# band4_0.net
KiCad netlist of a schematic drawn in EAGLE
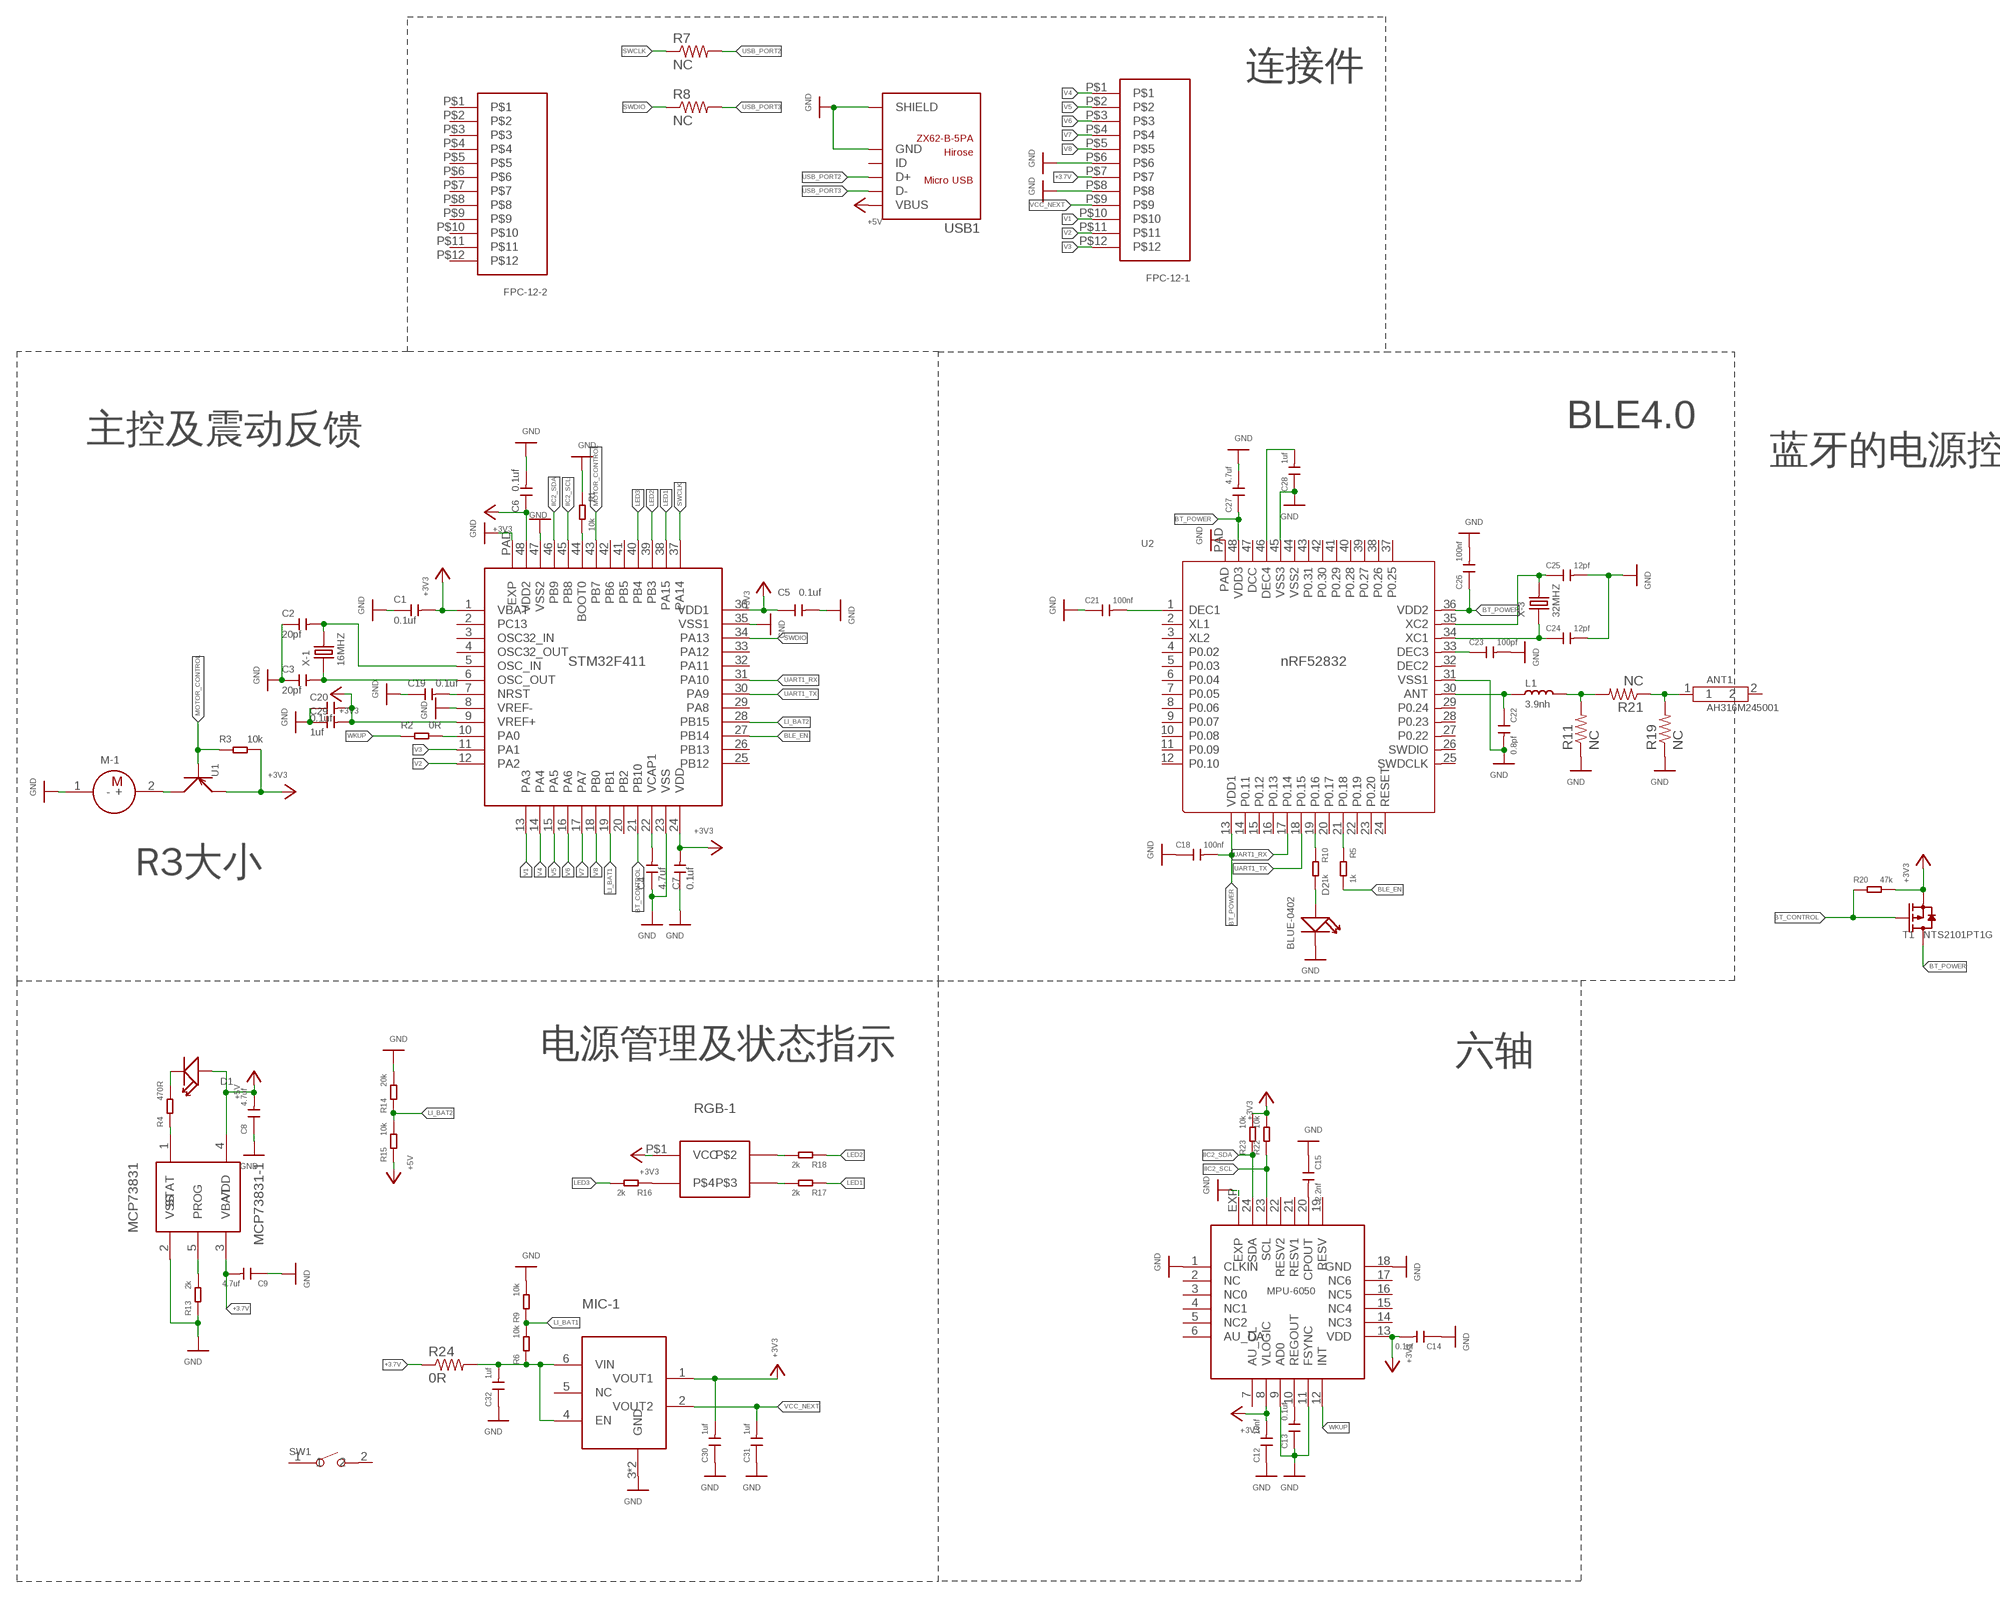
[diagram p0: schematic, sheet 1]

(export (version "E")
  (design (tool "Eeschema 10.0.6"))
  (components
    (comp (ref "ANT1")
      (value "AH316M245001")
      (footprint "eagle-import:ANT2-SMD-3.2X1.6X0.5MM")
      (fields (field (name "MPN") "AH316M245001-T"))
      (libsource (lib "eagle-import") (part "ANTENNA-2.4GHZ-AH316M245001-T"))
    )
    (comp (ref "C1")
      (value "0.1uf")
      (footprint "eagle-import:C0402")
      (fields (field (name "MPN") "CC0402BRNPO9BNR50"))
      (libsource (lib "eagle-import") (part "C(0402)"))
    )
    (comp (ref "C2")
      (value "20pf")
      (footprint "eagle-import:C0402")
      (fields (field (name "MPN") "CC0402BRNPO9BNR50"))
      (libsource (lib "eagle-import") (part "C(0402)"))
    )
    (comp (ref "C3")
      (value "20pf")
      (footprint "eagle-import:C0402")
      (fields (field (name "MPN") "CC0402BRNPO9BNR50"))
      (libsource (lib "eagle-import") (part "C(0402)"))
    )
    (comp (ref "C4")
      (value "4.7uf")
      (footprint "eagle-import:C0402")
      (fields (field (name "MPN") "CC0402BRNPO9BNR50"))
      (libsource (lib "eagle-import") (part "C(0402)"))
    )
    (comp (ref "C5")
      (value "0.1uf")
      (footprint "eagle-import:C0402")
      (fields (field (name "MPN") "CC0402BRNPO9BNR50"))
      (libsource (lib "eagle-import") (part "C(0402)"))
    )
    (comp (ref "C6")
      (value "0.1uf")
      (footprint "eagle-import:C0402")
      (fields (field (name "MPN") "CC0402BRNPO9BNR50"))
      (libsource (lib "eagle-import") (part "C(0402)"))
    )
    (comp (ref "C7")
      (value "0.1uf")
      (footprint "eagle-import:C0402")
      (fields (field (name "MPN") "CC0402BRNPO9BNR50"))
      (libsource (lib "eagle-import") (part "C(0402)"))
    )
    (comp (ref "C8")
      (value "4.7uf")
      (footprint "eagle-import:C0402")
      (fields (field (name "MPN") "CC0402BRNPO9BNR50"))
      (libsource (lib "eagle-import") (part "C(0402)"))
    )
    (comp (ref "C9")
      (value "4.7uf")
      (footprint "eagle-import:C0402")
      (fields (field (name "MPN") "CC0402BRNPO9BNR50"))
      (libsource (lib "eagle-import") (part "C(0402)"))
    )
    (comp (ref "C12")
      (value "10nf")
      (footprint "eagle-import:C0402")
      (fields (field (name "MPN") "CC0402BRNPO9BNR50"))
      (libsource (lib "eagle-import") (part "C(0402)"))
    )
    (comp (ref "C13")
      (value "0.1uf")
      (footprint "eagle-import:C0402")
      (fields (field (name "MPN") "CC0402BRNPO9BNR50"))
      (libsource (lib "eagle-import") (part "C(0402)"))
    )
    (comp (ref "C14")
      (value "0.1uf")
      (footprint "eagle-import:C0402")
      (fields (field (name "MPN") "CC0402BRNPO9BNR50"))
      (libsource (lib "eagle-import") (part "C(0402)"))
    )
    (comp (ref "C15")
      (value "2.2nf")
      (footprint "eagle-import:C0402")
      (fields (field (name "MPN") "CC0402BRNPO9BNR50"))
      (libsource (lib "eagle-import") (part "C(0402)"))
    )
    (comp (ref "C18")
      (value "100nf")
      (footprint "eagle-import:C0402")
      (fields (field (name "MPN") "CC0402BRNPO9BNR50"))
      (libsource (lib "eagle-import") (part "C(0402)"))
    )
    (comp (ref "C19")
      (value "0.1uf")
      (footprint "eagle-import:C0402")
      (fields (field (name "MPN") "CC0402BRNPO9BNR50"))
      (libsource (lib "eagle-import") (part "C(0402)"))
    )
    (comp (ref "C20")
      (value "0.1uf")
      (footprint "eagle-import:C0402")
      (fields (field (name "MPN") "CC0402BRNPO9BNR50"))
      (libsource (lib "eagle-import") (part "C(0402)"))
    )
    (comp (ref "C21")
      (value "100nf")
      (footprint "eagle-import:C0402")
      (fields (field (name "MPN") "CC0402BRNPO9BNR50"))
      (libsource (lib "eagle-import") (part "C(0402)"))
    )
    (comp (ref "C22")
      (value "0.8pf")
      (footprint "eagle-import:C0402")
      (fields (field (name "MPN") "CC0402BRNPO9BNR50"))
      (libsource (lib "eagle-import") (part "C(0402)"))
    )
    (comp (ref "C23")
      (value "100pf")
      (footprint "eagle-import:C0402")
      (fields (field (name "MPN") "CC0402BRNPO9BNR50"))
      (libsource (lib "eagle-import") (part "C(0402)"))
    )
    (comp (ref "C24")
      (value "12pf")
      (footprint "eagle-import:C0402")
      (fields (field (name "MPN") "CC0402BRNPO9BNR50"))
      (libsource (lib "eagle-import") (part "C(0402)"))
    )
    (comp (ref "C25")
      (value "12pf")
      (footprint "eagle-import:C0402")
      (fields (field (name "MPN") "CC0402BRNPO9BNR50"))
      (libsource (lib "eagle-import") (part "C(0402)"))
    )
    (comp (ref "C26")
      (value "100nf")
      (footprint "eagle-import:C0402")
      (fields (field (name "MPN") "CC0402BRNPO9BNR50"))
      (libsource (lib "eagle-import") (part "C(0402)"))
    )
    (comp (ref "C27")
      (value "4.7uf")
      (footprint "eagle-import:C0402")
      (fields (field (name "MPN") "CC0402BRNPO9BNR50"))
      (libsource (lib "eagle-import") (part "C(0402)"))
    )
    (comp (ref "C28")
      (value "1uf")
      (footprint "eagle-import:C0402")
      (fields (field (name "MPN") "CC0402BRNPO9BNR50"))
      (libsource (lib "eagle-import") (part "C(0402)"))
    )
    (comp (ref "C29")
      (value "1uf")
      (footprint "eagle-import:C0402")
      (fields (field (name "MPN") "CC0402BRNPO9BNR50"))
      (libsource (lib "eagle-import") (part "C(0402)"))
    )
    (comp (ref "C30")
      (value "1uf")
      (footprint "eagle-import:C0402")
      (fields (field (name "MPN") "CC0402BRNPO9BNR50"))
      (libsource (lib "eagle-import") (part "C(0402)"))
    )
    (comp (ref "C31")
      (value "1uf")
      (footprint "eagle-import:C0402")
      (fields (field (name "MPN") "CC0402BRNPO9BNR50"))
      (libsource (lib "eagle-import") (part "C(0402)"))
    )
    (comp (ref "C32")
      (value "1uf")
      (footprint "eagle-import:C0402")
      (fields (field (name "MPN") "CC0402BRNPO9BNR50"))
      (libsource (lib "eagle-import") (part "C(0402)"))
    )
    (comp (ref "D1")
      (value "LED-(0402)")
      (footprint "eagle-import:LED-0402")
      (fields (field (name "MPN") "BL-HB337A-AV-TRB"))
      (libsource (lib "eagle-import") (part "LED-(0402)"))
    )
    (comp (ref "D2")
      (value "BLUE-0402")
      (footprint "eagle-import:LED-0402")
      (fields (field (name "MPN") "BL-HB337A-AV-TRB"))
      (libsource (lib "eagle-import") (part "LED-(0402)"))
    )
    (comp (ref "FPC-12-1")
      (value "FPC-12")
      (footprint "eagle-import:FPC-12")
      (libsource (lib "eagle-import") (part "FPC-12"))
    )
    (comp (ref "FPC-12-2")
      (value "FPC-12")
      (footprint "eagle-import:FPC-12")
      (libsource (lib "eagle-import") (part "FPC-12"))
    )
    (comp (ref "L1")
      (value "3.9nh")
      (footprint "eagle-import:L0402")
      (libsource (lib "eagle-import") (part "INDUCTOR(0402)"))
    )
    (comp (ref "M-1")
      (value "MOTOR")
      (footprint "eagle-import:MOTOR")
      (libsource (lib "eagle-import") (part "MOTOR"))
    )
    (comp (ref "MCP73831-1")
      (value "MCP73831")
      (footprint "eagle-import:SOT23-5")
      (libsource (lib "eagle-import") (part "MCP73831"))
    )
    (comp (ref "MCU-1")
      (value "STM32F411")
      (footprint "eagle-import:QFN48G-0.5-7X7MM")
      (libsource (lib "eagle-import") (part "STM32F411"))
    )
    (comp (ref "MIC-1")
      (value "MIC5528")
      (footprint "eagle-import:THIN-DFN")
      (libsource (lib "eagle-import") (part "MIC5528"))
    )
    (comp (ref "MPU6050-1")
      (value "MPU-6050")
      (footprint "eagle-import:QFN24-4X4")
      (libsource (lib "eagle-import") (part "MPU-6050"))
    )
    (comp (ref "R1")
      (value "10k")
      (footprint "eagle-import:R0402")
      (fields (field (name "MPN") "RC0402JR-070RL"))
      (libsource (lib "eagle-import") (part "RES-(0402)"))
    )
    (comp (ref "R2")
      (value "0R")
      (footprint "eagle-import:R0402")
      (fields (field (name "MPN") "RC0402JR-070RL"))
      (libsource (lib "eagle-import") (part "RES-(0402)"))
    )
    (comp (ref "R3")
      (value "10k")
      (footprint "eagle-import:R0402")
      (fields (field (name "MPN") "RC0402JR-070RL"))
      (libsource (lib "eagle-import") (part "RES-(0402)"))
    )
    (comp (ref "R4")
      (value "470R")
      (footprint "eagle-import:R0402")
      (fields (field (name "MPN") "RC0402JR-070RL"))
      (libsource (lib "eagle-import") (part "RES-(0402)"))
    )
    (comp (ref "R5")
      (value "1k")
      (footprint "eagle-import:R0402")
      (fields (field (name "MPN") "RC0402JR-070RL"))
      (libsource (lib "eagle-import") (part "RES-(0402)"))
    )
    (comp (ref "R6")
      (value "10k")
      (footprint "eagle-import:R0402")
      (fields (field (name "MPN") "RC0402JR-070RL"))
      (libsource (lib "eagle-import") (part "RES-(0402)"))
    )
    (comp (ref "R7")
      (value "NC")
      (footprint "eagle-import:0201")
      (libsource (lib "eagle-import") (part "R_0201"))
    )
    (comp (ref "R8")
      (value "NC")
      (footprint "eagle-import:0201")
      (libsource (lib "eagle-import") (part "R_0201"))
    )
    (comp (ref "R9")
      (value "10k")
      (footprint "eagle-import:R0402")
      (fields (field (name "MPN") "RC0402JR-070RL"))
      (libsource (lib "eagle-import") (part "RES-(0402)"))
    )
    (comp (ref "R10")
      (value "1k")
      (footprint "eagle-import:R0402")
      (fields (field (name "MPN") "RC0402JR-070RL"))
      (libsource (lib "eagle-import") (part "RES-(0402)"))
    )
    (comp (ref "R11")
      (value "NC")
      (footprint "eagle-import:0201")
      (libsource (lib "eagle-import") (part "R_0201"))
    )
    (comp (ref "R13")
      (value "2k")
      (footprint "eagle-import:R0402")
      (fields (field (name "MPN") "RC0402JR-070RL"))
      (libsource (lib "eagle-import") (part "RES-(0402)"))
    )
    (comp (ref "R14")
      (value "20k")
      (footprint "eagle-import:R0402")
      (fields (field (name "MPN") "RC0402JR-070RL"))
      (libsource (lib "eagle-import") (part "RES-(0402)"))
    )
    (comp (ref "R15")
      (value "10k")
      (footprint "eagle-import:R0402")
      (fields (field (name "MPN") "RC0402JR-070RL"))
      (libsource (lib "eagle-import") (part "RES-(0402)"))
    )
    (comp (ref "R16")
      (value "2k")
      (footprint "eagle-import:R0402")
      (fields (field (name "MPN") "RC0402JR-070RL"))
      (libsource (lib "eagle-import") (part "RES-(0402)"))
    )
    (comp (ref "R17")
      (value "2k")
      (footprint "eagle-import:R0402")
      (fields (field (name "MPN") "RC0402JR-070RL"))
      (libsource (lib "eagle-import") (part "RES-(0402)"))
    )
    (comp (ref "R18")
      (value "2k")
      (footprint "eagle-import:R0402")
      (fields (field (name "MPN") "RC0402JR-070RL"))
      (libsource (lib "eagle-import") (part "RES-(0402)"))
    )
    (comp (ref "R19")
      (value "NC")
      (footprint "eagle-import:0201")
      (libsource (lib "eagle-import") (part "R_0201"))
    )
    (comp (ref "R20")
      (value "47k")
      (footprint "eagle-import:R0402")
      (fields (field (name "MPN") "RC0402JR-070RL"))
      (libsource (lib "eagle-import") (part "RES-(0402)"))
    )
    (comp (ref "R21")
      (value "NC")
      (footprint "eagle-import:0201")
      (libsource (lib "eagle-import") (part "R_0201"))
    )
    (comp (ref "R22")
      (value "10k")
      (footprint "eagle-import:R0402")
      (fields (field (name "MPN") "RC0402JR-070RL"))
      (libsource (lib "eagle-import") (part "RES-(0402)"))
    )
    (comp (ref "R23")
      (value "10k")
      (footprint "eagle-import:R0402")
      (fields (field (name "MPN") "RC0402JR-070RL"))
      (libsource (lib "eagle-import") (part "RES-(0402)"))
    )
    (comp (ref "R24")
      (value "0R")
      (footprint "eagle-import:0201")
      (libsource (lib "eagle-import") (part "R_0201"))
    )
    (comp (ref "RGB-1")
      (value "RGB-LED")
      (footprint "eagle-import:RGB-LED")
      (libsource (lib "eagle-import") (part "RGB-LED"))
    )
    (comp (ref "SW1")
      (value "SMD-BUTTON(2P-6.0X3.0X2.5MM)-DHT-1163S")
      (footprint "eagle-import:SW2-4.0-6.0X3.0X2.5MM")
      (libsource (lib "eagle-import") (part "SMD-BUTTON(2P-6.0X3.0X2.5MM)-DHT-1163S"))
    )
    (comp (ref "T1")
      (value "NTS2101PT1G")
      (footprint "eagle-import:SC70")
      (libsource (lib "eagle-import") (part "NTS2101PT1G"))
    )
    (comp (ref "U1")
      (value "PNP")
      (footprint "eagle-import:PNP")
      (libsource (lib "eagle-import") (part "PNP"))
    )
    (comp (ref "U2")
      (value "RF-51822")
      (footprint "eagle-import:QFN48G-0.4-6X6MM")
      (libsource (lib "eagle-import") (part "IC-NRF-52832(QFN48)"))
    )
    (comp (ref "USB1")
      (value "ZX62-B-5PA")
      (footprint "eagle-import:MICRO-USB5+6P-SMD-0.65-AB")
      (libsource (lib "eagle-import") (part "MICRO-USB-SMD(ZX62-B-5PA)"))
    )
    (comp (ref "X-1")
      (value "16MHZ")
      (footprint "eagle-import:16MHZ")
      (libsource (lib "eagle-import") (part "16MHZ"))
    )
    (comp (ref "X-3")
      (value "32MHZ")
      (footprint "eagle-import:16MHZ")
      (libsource (lib "eagle-import") (part "16MHZ"))
    )
  )
  (nets
    (net (code "1") (name "+3.7V") (class "Default")
      (node (ref "C9") (pin "2") (pinfunction "2_2") (pintype "passive"))
      (node (ref "FPC-12-1") (pin "P$7") (pinfunction "P$7_P$7") (pintype "bidirectional"))
      (node (ref "MCP73831-1") (pin "3") (pinfunction "VBAT_3") (pintype "bidirectional"))
      (node (ref "R24") (pin "1") (pinfunction "1_1") (pintype "passive"))
    )
    (net (code "2") (name "+3V3") (class "Default")
      (node (ref "C1") (pin "2") (pinfunction "2_2") (pintype "passive"))
      (node (ref "C12") (pin "2") (pinfunction "2_2") (pintype "passive"))
      (node (ref "C14") (pin "2") (pinfunction "2_2") (pintype "passive"))
      (node (ref "C20") (pin "2") (pinfunction "2_2") (pintype "passive"))
      (node (ref "C29") (pin "2") (pinfunction "2_2") (pintype "passive"))
      (node (ref "C30") (pin "2") (pinfunction "2_2") (pintype "passive"))
      (node (ref "C5") (pin "1") (pinfunction "1_1") (pintype "passive"))
      (node (ref "C6") (pin "1") (pinfunction "1_1") (pintype "passive"))
      (node (ref "C7") (pin "2") (pinfunction "2_2") (pintype "passive"))
      (node (ref "MCU-1") (pin "1") (pinfunction "VBAT_1") (pintype "bidirectional"))
      (node (ref "MCU-1") (pin "24") (pinfunction "VDD_24") (pintype "bidirectional"))
      (node (ref "MCU-1") (pin "36") (pinfunction "VDD1_36") (pintype "bidirectional"))
      (node (ref "MCU-1") (pin "48") (pinfunction "VDD2_48") (pintype "bidirectional"))
      (node (ref "MCU-1") (pin "9") (pinfunction "VREF+_9") (pintype "bidirectional"))
      (node (ref "MIC-1") (pin "1") (pinfunction "VOUT1_1") (pintype "bidirectional"))
      (node (ref "MPU6050-1") (pin "13") (pinfunction "VDD_13") (pintype "bidirectional"))
      (node (ref "MPU6050-1") (pin "8") (pinfunction "VLOGIC_8") (pintype "bidirectional"))
      (node (ref "R20") (pin "2") (pinfunction "2_2") (pintype "passive"))
      (node (ref "R22") (pin "2") (pinfunction "2_2") (pintype "passive"))
      (node (ref "R23") (pin "2") (pinfunction "2_2") (pintype "passive"))
      (node (ref "R3") (pin "2") (pinfunction "2_2") (pintype "passive"))
      (node (ref "RGB-1") (pin "P$1") (pinfunction "VCC_P$1") (pintype "bidirectional"))
      (node (ref "T1") (pin "2") (pinfunction "S_2") (pintype "passive"))
      (node (ref "U1") (pin "2") (pinfunction "E_2") (pintype "passive"))
    )
    (net (code "3") (name "+5V") (class "Default")
      (node (ref "C8") (pin "2") (pinfunction "2_2") (pintype "passive"))
      (node (ref "D1") (pin "+") (pinfunction "+_+") (pintype "passive"))
      (node (ref "MCP73831-1") (pin "4") (pinfunction "VDD_4") (pintype "bidirectional"))
      (node (ref "R15") (pin "1") (pinfunction "1_1") (pintype "passive"))
      (node (ref "USB1") (pin "1") (pinfunction "VBUS_1") (pintype "power_in"))
    )
    (net (code "4") (name "BLE_EN") (class "Default")
      (node (ref "MCU-1") (pin "27") (pinfunction "PB14_27") (pintype "bidirectional"))
      (node (ref "R5") (pin "2") (pinfunction "2_2") (pintype "passive"))
    )
    (net (code "5") (name "BT_CONTROL") (class "Default")
      (node (ref "MCU-1") (pin "21") (pinfunction "PB10_21") (pintype "bidirectional"))
      (node (ref "R20") (pin "1") (pinfunction "1_1") (pintype "passive"))
      (node (ref "T1") (pin "1") (pinfunction "G_1") (pintype "passive"))
    )
    (net (code "6") (name "BT_POWER") (class "Default")
      (node (ref "C18") (pin "2") (pinfunction "2_2") (pintype "passive"))
      (node (ref "C26") (pin "1") (pinfunction "1_1") (pintype "passive"))
      (node (ref "C27") (pin "1") (pinfunction "1_1") (pintype "passive"))
      (node (ref "T1") (pin "3") (pinfunction "D_3") (pintype "passive"))
      (node (ref "U2") (pin "13") (pinfunction "VDD1_13") (pintype "bidirectional"))
      (node (ref "U2") (pin "36") (pinfunction "VDD2_36") (pintype "bidirectional"))
      (node (ref "U2") (pin "48") (pinfunction "VDD3_48") (pintype "bidirectional"))
    )
    (net (code "7") (name "GND") (class "Default")
      (node (ref "C1") (pin "1") (pinfunction "1_1") (pintype "passive"))
      (node (ref "C12") (pin "1") (pinfunction "1_1") (pintype "passive"))
      (node (ref "C13") (pin "1") (pinfunction "1_1") (pintype "passive"))
      (node (ref "C14") (pin "1") (pinfunction "1_1") (pintype "passive"))
      (node (ref "C15") (pin "1") (pinfunction "1_1") (pintype "passive"))
      (node (ref "C18") (pin "1") (pinfunction "1_1") (pintype "passive"))
      (node (ref "C19") (pin "1") (pinfunction "1_1") (pintype "passive"))
      (node (ref "C2") (pin "1") (pinfunction "1_1") (pintype "passive"))
      (node (ref "C20") (pin "1") (pinfunction "1_1") (pintype "passive"))
      (node (ref "C21") (pin "1") (pinfunction "1_1") (pintype "passive"))
      (node (ref "C22") (pin "2") (pinfunction "2_2") (pintype "passive"))
      (node (ref "C23") (pin "2") (pinfunction "2_2") (pintype "passive"))
      (node (ref "C24") (pin "2") (pinfunction "2_2") (pintype "passive"))
      (node (ref "C25") (pin "2") (pinfunction "2_2") (pintype "passive"))
      (node (ref "C26") (pin "2") (pinfunction "2_2") (pintype "passive"))
      (node (ref "C27") (pin "2") (pinfunction "2_2") (pintype "passive"))
      (node (ref "C28") (pin "1") (pinfunction "1_1") (pintype "passive"))
      (node (ref "C29") (pin "1") (pinfunction "1_1") (pintype "passive"))
      (node (ref "C3") (pin "1") (pinfunction "1_1") (pintype "passive"))
      (node (ref "C30") (pin "1") (pinfunction "1_1") (pintype "passive"))
      (node (ref "C31") (pin "1") (pinfunction "1_1") (pintype "passive"))
      (node (ref "C32") (pin "1") (pinfunction "1_1") (pintype "passive"))
      (node (ref "C4") (pin "1") (pinfunction "1_1") (pintype "passive"))
      (node (ref "C5") (pin "2") (pinfunction "2_2") (pintype "passive"))
      (node (ref "C6") (pin "2") (pinfunction "2_2") (pintype "passive"))
      (node (ref "C7") (pin "1") (pinfunction "1_1") (pintype "passive"))
      (node (ref "C8") (pin "1") (pinfunction "1_1") (pintype "passive"))
      (node (ref "C9") (pin "1") (pinfunction "1_1") (pintype "passive"))
      (node (ref "D2") (pin "-") (pinfunction "-_-") (pintype "passive"))
      (node (ref "FPC-12-1") (pin "P$6") (pinfunction "P$6_P$6") (pintype "bidirectional"))
      (node (ref "FPC-12-1") (pin "P$8") (pinfunction "P$8_P$8") (pintype "bidirectional"))
      (node (ref "M-1") (pin "1") (pinfunction "-_1") (pintype "bidirectional"))
      (node (ref "MCP73831-1") (pin "2") (pinfunction "VSS_2") (pintype "bidirectional"))
      (node (ref "MCU-1") (pin "23") (pinfunction "VSS_23") (pintype "bidirectional"))
      (node (ref "MCU-1") (pin "35") (pinfunction "VSS1_35") (pintype "bidirectional"))
      (node (ref "MCU-1") (pin "47") (pinfunction "VSS2_47") (pintype "bidirectional"))
      (node (ref "MCU-1") (pin "8") (pinfunction "VREF-_8") (pintype "bidirectional"))
      (node (ref "MCU-1") (pin "PAD") (pinfunction "EXP_PAD") (pintype "bidirectional"))
      (node (ref "MIC-1") (pin "3") (pinfunction "GND_3") (pintype "bidirectional"))
      (node (ref "MIC-1") (pin "7") (pinfunction "GND_7") (pintype "bidirectional"))
      (node (ref "MPU6050-1") (pin "1") (pinfunction "CLKIN_1") (pintype "bidirectional"))
      (node (ref "MPU6050-1") (pin "11") (pinfunction "FSYNC_11") (pintype "bidirectional"))
      (node (ref "MPU6050-1") (pin "18") (pinfunction "GND_18") (pintype "bidirectional"))
      (node (ref "MPU6050-1") (pin "9") (pinfunction "AD0_9") (pintype "bidirectional"))
      (node (ref "MPU6050-1") (pin "EXP") (pinfunction "EXP_EXP") (pintype "bidirectional"))
      (node (ref "R1") (pin "1") (pinfunction "1_1") (pintype "passive"))
      (node (ref "R11") (pin "1") (pinfunction "1_1") (pintype "passive"))
      (node (ref "R13") (pin "1") (pinfunction "1_1") (pintype "passive"))
      (node (ref "R14") (pin "2") (pinfunction "2_2") (pintype "passive"))
      (node (ref "R19") (pin "1") (pinfunction "1_1") (pintype "passive"))
      (node (ref "R9") (pin "2") (pinfunction "2_2") (pintype "passive"))
      (node (ref "U2") (pin "31") (pinfunction "VSS1_31") (pintype "bidirectional"))
      (node (ref "U2") (pin "45") (pinfunction "VSS3_45") (pintype "bidirectional"))
      (node (ref "U2") (pin "PAD") (pinfunction "PAD_PAD") (pintype "bidirectional"))
      (node (ref "USB1") (pin "5") (pinfunction "GND_5") (pintype "power_in"))
      (node (ref "USB1") (pin "P1") (pinfunction "SHIELD_P1") (pintype "power_in"))
      (node (ref "USB1") (pin "P2") (pinfunction "SHIELD_P2") (pintype "power_in"))
      (node (ref "USB1") (pin "P3") (pinfunction "SHIELD_P3") (pintype "power_in"))
      (node (ref "USB1") (pin "P4") (pinfunction "SHIELD_P4") (pintype "power_in"))
      (node (ref "USB1") (pin "P5") (pinfunction "SHIELD_P5") (pintype "power_in"))
      (node (ref "USB1") (pin "P6") (pinfunction "SHIELD_P6") (pintype "power_in"))
    )
    (net (code "8") (name "IIC2_SCL") (class "Default")
      (node (ref "MCU-1") (pin "45") (pinfunction "PB8_45") (pintype "bidirectional"))
      (node (ref "MPU6050-1") (pin "23") (pinfunction "SCL_23") (pintype "bidirectional"))
      (node (ref "R22") (pin "1") (pinfunction "1_1") (pintype "passive"))
    )
    (net (code "9") (name "IIC2_SDA") (class "Default")
      (node (ref "MCU-1") (pin "46") (pinfunction "PB9_46") (pintype "bidirectional"))
      (node (ref "MPU6050-1") (pin "24") (pinfunction "SDA_24") (pintype "bidirectional"))
      (node (ref "R23") (pin "1") (pinfunction "1_1") (pintype "passive"))
    )
    (net (code "10") (name "LED1") (class "Default")
      (node (ref "MCU-1") (pin "38") (pinfunction "PA15_38") (pintype "bidirectional"))
      (node (ref "R17") (pin "1") (pinfunction "1_1") (pintype "passive"))
    )
    (net (code "11") (name "LED2") (class "Default")
      (node (ref "MCU-1") (pin "39") (pinfunction "PB3_39") (pintype "bidirectional"))
      (node (ref "R18") (pin "1") (pinfunction "1_1") (pintype "passive"))
    )
    (net (code "12") (name "LED3") (class "Default")
      (node (ref "MCU-1") (pin "40") (pinfunction "PB4_40") (pintype "bidirectional"))
      (node (ref "R16") (pin "2") (pinfunction "2_2") (pintype "passive"))
    )
    (net (code "13") (name "LI_BAT1") (class "Default")
      (node (ref "MCU-1") (pin "19") (pinfunction "PB1_19") (pintype "bidirectional"))
      (node (ref "R6") (pin "2") (pinfunction "2_2") (pintype "passive"))
      (node (ref "R9") (pin "1") (pinfunction "1_1") (pintype "passive"))
    )
    (net (code "14") (name "LI_BAT2") (class "Default")
      (node (ref "MCU-1") (pin "28") (pinfunction "PB15_28") (pintype "bidirectional"))
      (node (ref "R14") (pin "1") (pinfunction "1_1") (pintype "passive"))
      (node (ref "R15") (pin "2") (pinfunction "2_2") (pintype "passive"))
    )
    (net (code "15") (name "MOTOR_CONTROL") (class "Default")
      (node (ref "MCU-1") (pin "43") (pinfunction "PB7_43") (pintype "bidirectional"))
      (node (ref "R3") (pin "1") (pinfunction "1_1") (pintype "passive"))
      (node (ref "U1") (pin "1") (pinfunction "B_1") (pintype "passive"))
    )
    (net (code "16") (name "Net-(ANT1-Pad1)") (class "Default")
      (node (ref "ANT1") (pin "1") (pinfunction "1_1") (pintype "bidirectional"))
      (node (ref "R19") (pin "2") (pinfunction "2_2") (pintype "passive"))
      (node (ref "R21") (pin "1") (pinfunction "1_1") (pintype "passive"))
    )
    (net (code "17") (name "Net-(D1-Pad-)") (class "Default")
      (node (ref "D1") (pin "-") (pinfunction "-_-") (pintype "passive"))
      (node (ref "R4") (pin "2") (pinfunction "2_2") (pintype "passive"))
    )
    (net (code "18") (name "Net-(D2-Pad+)") (class "Default")
      (node (ref "D2") (pin "+") (pinfunction "+_+") (pintype "passive"))
      (node (ref "R10") (pin "2") (pinfunction "2_2") (pintype "passive"))
    )
    (net (code "19") (name "Net-(L1-Pad2)") (class "Default")
      (node (ref "L1") (pin "2") (pinfunction "2_2") (pintype "passive"))
      (node (ref "R11") (pin "2") (pinfunction "2_2") (pintype "passive"))
      (node (ref "R21") (pin "2") (pinfunction "2_2") (pintype "passive"))
    )
    (net (code "20") (name "Net-(M-1-+)") (class "Default")
      (node (ref "M-1") (pin "2") (pinfunction "+_2") (pintype "bidirectional"))
      (node (ref "U1") (pin "3") (pinfunction "C_3") (pintype "passive"))
    )
    (net (code "21") (name "Net-(MCP73831-1-PROG)") (class "Default")
      (node (ref "MCP73831-1") (pin "5") (pinfunction "PROG_5") (pintype "bidirectional"))
      (node (ref "R13") (pin "2") (pinfunction "2_2") (pintype "passive"))
    )
    (net (code "22") (name "Net-(MCP73831-1-STAT)") (class "Default")
      (node (ref "MCP73831-1") (pin "1") (pinfunction "STAT_1") (pintype "bidirectional"))
      (node (ref "R4") (pin "1") (pinfunction "1_1") (pintype "passive"))
    )
    (net (code "23") (name "Net-(MCU-1-BOOT0)") (class "Default")
      (node (ref "MCU-1") (pin "44") (pinfunction "BOOT0_44") (pintype "bidirectional"))
      (node (ref "R1") (pin "2") (pinfunction "2_2") (pintype "passive"))
    )
    (net (code "24") (name "Net-(MCU-1-NRST)") (class "Default")
      (node (ref "C19") (pin "2") (pinfunction "2_2") (pintype "passive"))
      (node (ref "MCU-1") (pin "7") (pinfunction "NRST_7") (pintype "bidirectional"))
    )
    (net (code "25") (name "Net-(MCU-1-OSC_IN)") (class "Default")
      (node (ref "C2") (pin "2") (pinfunction "2_2") (pintype "passive"))
      (node (ref "MCU-1") (pin "5") (pinfunction "OSC_IN_5") (pintype "bidirectional"))
      (node (ref "X-1") (pin "3") (pinfunction "2_3") (pintype "passive"))
    )
    (net (code "26") (name "Net-(MCU-1-OSC_OUT)") (class "Default")
      (node (ref "C3") (pin "2") (pinfunction "2_2") (pintype "passive"))
      (node (ref "MCU-1") (pin "6") (pinfunction "OSC_OUT_6") (pintype "bidirectional"))
      (node (ref "X-1") (pin "1") (pinfunction "1_1") (pintype "passive"))
    )
    (net (code "27") (name "Net-(MCU-1-PA0)") (class "Default")
      (node (ref "MCU-1") (pin "10") (pinfunction "PA0_10") (pintype "bidirectional"))
      (node (ref "R2") (pin "2") (pinfunction "2_2") (pintype "passive"))
    )
    (net (code "28") (name "Net-(MCU-1-VCAP1)") (class "Default")
      (node (ref "C4") (pin "2") (pinfunction "2_2") (pintype "passive"))
      (node (ref "MCU-1") (pin "22") (pinfunction "VCAP1_22") (pintype "bidirectional"))
    )
    (net (code "29") (name "Net-(MIC-1-EN)") (class "Default")
      (node (ref "C32") (pin "2") (pinfunction "2_2") (pintype "passive"))
      (node (ref "MIC-1") (pin "4") (pinfunction "EN_4") (pintype "bidirectional"))
      (node (ref "MIC-1") (pin "6") (pinfunction "VIN_6") (pintype "bidirectional"))
      (node (ref "R24") (pin "2") (pinfunction "2_2") (pintype "passive"))
      (node (ref "R6") (pin "1") (pinfunction "1_1") (pintype "passive"))
    )
    (net (code "30") (name "Net-(MPU6050-1-CPOUT)") (class "Default")
      (node (ref "C15") (pin "2") (pinfunction "2_2") (pintype "passive"))
      (node (ref "MPU6050-1") (pin "20") (pinfunction "CPOUT_20") (pintype "bidirectional"))
    )
    (net (code "31") (name "Net-(MPU6050-1-REGOUT)") (class "Default")
      (node (ref "C13") (pin "2") (pinfunction "2_2") (pintype "passive"))
      (node (ref "MPU6050-1") (pin "10") (pinfunction "REGOUT_10") (pintype "bidirectional"))
    )
    (net (code "32") (name "Net-(R16-Pad1)") (class "Default")
      (node (ref "R16") (pin "1") (pinfunction "1_1") (pintype "passive"))
      (node (ref "RGB-1") (pin "P$4") (pinfunction "P$4_P$4") (pintype "bidirectional"))
    )
    (net (code "33") (name "Net-(R17-Pad2)") (class "Default")
      (node (ref "R17") (pin "2") (pinfunction "2_2") (pintype "passive"))
      (node (ref "RGB-1") (pin "P$3") (pinfunction "P$3_P$3") (pintype "bidirectional"))
    )
    (net (code "34") (name "Net-(R18-Pad2)") (class "Default")
      (node (ref "R18") (pin "2") (pinfunction "2_2") (pintype "passive"))
      (node (ref "RGB-1") (pin "P$2") (pinfunction "P$2_P$2") (pintype "bidirectional"))
    )
    (net (code "35") (name "Net-(U2-ANT)") (class "Default")
      (node (ref "C22") (pin "1") (pinfunction "1_1") (pintype "passive"))
      (node (ref "L1") (pin "1") (pinfunction "1_1") (pintype "passive"))
      (node (ref "U2") (pin "30") (pinfunction "ANT_30") (pintype "bidirectional"))
    )
    (net (code "36") (name "Net-(U2-DEC1)") (class "Default")
      (node (ref "C21") (pin "2") (pinfunction "2_2") (pintype "passive"))
      (node (ref "U2") (pin "1") (pinfunction "DEC1_1") (pintype "bidirectional"))
    )
    (net (code "37") (name "Net-(U2-DEC3)") (class "Default")
      (node (ref "C23") (pin "1") (pinfunction "1_1") (pintype "passive"))
      (node (ref "U2") (pin "33") (pinfunction "DEC3_33") (pintype "bidirectional"))
    )
    (net (code "38") (name "Net-(U2-DEC4)") (class "Default")
      (node (ref "C28") (pin "2") (pinfunction "2_2") (pintype "passive"))
      (node (ref "U2") (pin "46") (pinfunction "DEC4_46") (pintype "bidirectional"))
    )
    (net (code "39") (name "Net-(U2-P0.16)") (class "Default")
      (node (ref "R10") (pin "1") (pinfunction "1_1") (pintype "passive"))
      (node (ref "U2") (pin "19") (pinfunction "P0.16_19") (pintype "bidirectional"))
    )
    (net (code "40") (name "Net-(U2-P0.18)") (class "Default")
      (node (ref "R5") (pin "1") (pinfunction "1_1") (pintype "passive"))
      (node (ref "U2") (pin "21") (pinfunction "P0.18_21") (pintype "bidirectional"))
    )
    (net (code "41") (name "Net-(U2-XC1)") (class "Default")
      (node (ref "C24") (pin "1") (pinfunction "1_1") (pintype "passive"))
      (node (ref "U2") (pin "34") (pinfunction "XC1_34") (pintype "bidirectional"))
      (node (ref "X-3") (pin "1") (pinfunction "1_1") (pintype "passive"))
    )
    (net (code "42") (name "Net-(U2-XC2)") (class "Default")
      (node (ref "C25") (pin "1") (pinfunction "1_1") (pintype "passive"))
      (node (ref "U2") (pin "35") (pinfunction "XC2_35") (pintype "bidirectional"))
      (node (ref "X-3") (pin "3") (pinfunction "2_3") (pintype "passive"))
    )
    (net (code "43") (name "SWCLK") (class "Default")
      (node (ref "MCU-1") (pin "37") (pinfunction "PA14_37") (pintype "bidirectional"))
      (node (ref "R7") (pin "1") (pinfunction "1_1") (pintype "passive"))
    )
    (net (code "44") (name "SWDIO") (class "Default")
      (node (ref "MCU-1") (pin "34") (pinfunction "PA13_34") (pintype "bidirectional"))
      (node (ref "R8") (pin "1") (pinfunction "1_1") (pintype "passive"))
    )
    (net (code "45") (name "UART1_RX") (class "Default")
      (node (ref "MCU-1") (pin "31") (pinfunction "PA10_31") (pintype "bidirectional"))
      (node (ref "U2") (pin "17") (pinfunction "P0.14_17") (pintype "bidirectional"))
    )
    (net (code "46") (name "UART1_TX") (class "Default")
      (node (ref "MCU-1") (pin "30") (pinfunction "PA9_30") (pintype "bidirectional"))
      (node (ref "U2") (pin "18") (pinfunction "P0.15_18") (pintype "bidirectional"))
    )
    (net (code "47") (name "USB_PORT2") (class "Default")
      (node (ref "R7") (pin "2") (pinfunction "2_2") (pintype "passive"))
      (node (ref "USB1") (pin "3") (pinfunction "D+_3") (pintype "bidirectional"))
    )
    (net (code "48") (name "USB_PORT3") (class "Default")
      (node (ref "R8") (pin "2") (pinfunction "2_2") (pintype "passive"))
      (node (ref "USB1") (pin "2") (pinfunction "D-_2") (pintype "bidirectional"))
    )
    (net (code "49") (name "V1") (class "Default")
      (node (ref "FPC-12-1") (pin "P$10") (pinfunction "P$10_P$10") (pintype "bidirectional"))
      (node (ref "MCU-1") (pin "13") (pinfunction "PA3_13") (pintype "bidirectional"))
    )
    (net (code "50") (name "V2") (class "Default")
      (node (ref "FPC-12-1") (pin "P$11") (pinfunction "P$11_P$11") (pintype "bidirectional"))
      (node (ref "MCU-1") (pin "12") (pinfunction "PA2_12") (pintype "bidirectional"))
    )
    (net (code "51") (name "V3") (class "Default")
      (node (ref "FPC-12-1") (pin "P$12") (pinfunction "P$12_P$12") (pintype "bidirectional"))
      (node (ref "MCU-1") (pin "11") (pinfunction "PA1_11") (pintype "bidirectional"))
    )
    (net (code "52") (name "V4") (class "Default")
      (node (ref "FPC-12-1") (pin "P$1") (pinfunction "P$1_P$1") (pintype "bidirectional"))
      (node (ref "MCU-1") (pin "14") (pinfunction "PA4_14") (pintype "bidirectional"))
    )
    (net (code "53") (name "V5") (class "Default")
      (node (ref "FPC-12-1") (pin "P$2") (pinfunction "P$2_P$2") (pintype "bidirectional"))
      (node (ref "MCU-1") (pin "15") (pinfunction "PA5_15") (pintype "bidirectional"))
    )
    (net (code "54") (name "V6") (class "Default")
      (node (ref "FPC-12-1") (pin "P$3") (pinfunction "P$3_P$3") (pintype "bidirectional"))
      (node (ref "MCU-1") (pin "16") (pinfunction "PA6_16") (pintype "bidirectional"))
    )
    (net (code "55") (name "V7") (class "Default")
      (node (ref "FPC-12-1") (pin "P$4") (pinfunction "P$4_P$4") (pintype "bidirectional"))
      (node (ref "MCU-1") (pin "17") (pinfunction "PA7_17") (pintype "bidirectional"))
    )
    (net (code "56") (name "V8") (class "Default")
      (node (ref "FPC-12-1") (pin "P$5") (pinfunction "P$5_P$5") (pintype "bidirectional"))
      (node (ref "MCU-1") (pin "18") (pinfunction "PB0_18") (pintype "bidirectional"))
    )
    (net (code "57") (name "VCC_NEXT") (class "Default")
      (node (ref "C31") (pin "2") (pinfunction "2_2") (pintype "passive"))
      (node (ref "FPC-12-1") (pin "P$9") (pinfunction "P$9_P$9") (pintype "bidirectional"))
      (node (ref "MIC-1") (pin "2") (pinfunction "VOUT2_2") (pintype "bidirectional"))
    )
    (net (code "58") (name "WKUP") (class "Default")
      (node (ref "MPU6050-1") (pin "12") (pinfunction "INT_12") (pintype "bidirectional"))
      (node (ref "R2") (pin "1") (pinfunction "1_1") (pintype "passive"))
    )
    (net (code "59") (name "unconnected-(ANT1-Pad2)") (class "Default")
      (node (ref "ANT1") (pin "2") (pinfunction "2_2") (pintype "bidirectional"))
    )
    (net (code "60") (name "unconnected-(FPC-12-2-PadP$1)") (class "Default")
      (node (ref "FPC-12-2") (pin "P$1") (pinfunction "P$1_P$1") (pintype "bidirectional"))
    )
    (net (code "61") (name "unconnected-(FPC-12-2-PadP$2)") (class "Default")
      (node (ref "FPC-12-2") (pin "P$2") (pinfunction "P$2_P$2") (pintype "bidirectional"))
    )
    (net (code "62") (name "unconnected-(FPC-12-2-PadP$3)") (class "Default")
      (node (ref "FPC-12-2") (pin "P$3") (pinfunction "P$3_P$3") (pintype "bidirectional"))
    )
    (net (code "63") (name "unconnected-(FPC-12-2-PadP$4)") (class "Default")
      (node (ref "FPC-12-2") (pin "P$4") (pinfunction "P$4_P$4") (pintype "bidirectional"))
    )
    (net (code "64") (name "unconnected-(FPC-12-2-PadP$5)") (class "Default")
      (node (ref "FPC-12-2") (pin "P$5") (pinfunction "P$5_P$5") (pintype "bidirectional"))
    )
    (net (code "65") (name "unconnected-(FPC-12-2-PadP$6)") (class "Default")
      (node (ref "FPC-12-2") (pin "P$6") (pinfunction "P$6_P$6") (pintype "bidirectional"))
    )
    (net (code "66") (name "unconnected-(FPC-12-2-PadP$7)") (class "Default")
      (node (ref "FPC-12-2") (pin "P$7") (pinfunction "P$7_P$7") (pintype "bidirectional"))
    )
    (net (code "67") (name "unconnected-(FPC-12-2-PadP$8)") (class "Default")
      (node (ref "FPC-12-2") (pin "P$8") (pinfunction "P$8_P$8") (pintype "bidirectional"))
    )
    (net (code "68") (name "unconnected-(FPC-12-2-PadP$9)") (class "Default")
      (node (ref "FPC-12-2") (pin "P$9") (pinfunction "P$9_P$9") (pintype "bidirectional"))
    )
    (net (code "69") (name "unconnected-(FPC-12-2-PadP$10)") (class "Default")
      (node (ref "FPC-12-2") (pin "P$10") (pinfunction "P$10_P$10") (pintype "bidirectional"))
    )
    (net (code "70") (name "unconnected-(FPC-12-2-PadP$11)") (class "Default")
      (node (ref "FPC-12-2") (pin "P$11") (pinfunction "P$11_P$11") (pintype "bidirectional"))
    )
    (net (code "71") (name "unconnected-(FPC-12-2-PadP$12)") (class "Default")
      (node (ref "FPC-12-2") (pin "P$12") (pinfunction "P$12_P$12") (pintype "bidirectional"))
    )
    (net (code "72") (name "unconnected-(MCU-1-OSC32_IN-Pad3)") (class "Default")
      (node (ref "MCU-1") (pin "3") (pinfunction "OSC32_IN_3") (pintype "bidirectional"))
    )
    (net (code "73") (name "unconnected-(MCU-1-OSC32_OUT-Pad4)") (class "Default")
      (node (ref "MCU-1") (pin "4") (pinfunction "OSC32_OUT_4") (pintype "bidirectional"))
    )
    (net (code "74") (name "unconnected-(MCU-1-PA8-Pad29)") (class "Default")
      (node (ref "MCU-1") (pin "29") (pinfunction "PA8_29") (pintype "bidirectional"))
    )
    (net (code "75") (name "unconnected-(MCU-1-PA11-Pad32)") (class "Default")
      (node (ref "MCU-1") (pin "32") (pinfunction "PA11_32") (pintype "bidirectional"))
    )
    (net (code "76") (name "unconnected-(MCU-1-PA12-Pad33)") (class "Default")
      (node (ref "MCU-1") (pin "33") (pinfunction "PA12_33") (pintype "bidirectional"))
    )
    (net (code "77") (name "unconnected-(MCU-1-PB2-Pad20)") (class "Default")
      (node (ref "MCU-1") (pin "20") (pinfunction "PB2_20") (pintype "bidirectional"))
    )
    (net (code "78") (name "unconnected-(MCU-1-PB5-Pad41)") (class "Default")
      (node (ref "MCU-1") (pin "41") (pinfunction "PB5_41") (pintype "bidirectional"))
    )
    (net (code "79") (name "unconnected-(MCU-1-PB6-Pad42)") (class "Default")
      (node (ref "MCU-1") (pin "42") (pinfunction "PB6_42") (pintype "bidirectional"))
    )
    (net (code "80") (name "unconnected-(MCU-1-PB12-Pad25)") (class "Default")
      (node (ref "MCU-1") (pin "25") (pinfunction "PB12_25") (pintype "bidirectional"))
    )
    (net (code "81") (name "unconnected-(MCU-1-PB13-Pad26)") (class "Default")
      (node (ref "MCU-1") (pin "26") (pinfunction "PB13_26") (pintype "bidirectional"))
    )
    (net (code "82") (name "unconnected-(MCU-1-PC13-Pad2)") (class "Default")
      (node (ref "MCU-1") (pin "2") (pinfunction "PC13_2") (pintype "bidirectional"))
    )
    (net (code "83") (name "unconnected-(MIC-1-NC-Pad5)") (class "Default")
      (node (ref "MIC-1") (pin "5") (pinfunction "NC_5") (pintype "bidirectional"))
    )
    (net (code "84") (name "unconnected-(MPU6050-1-AU_CL-Pad7)") (class "Default")
      (node (ref "MPU6050-1") (pin "7") (pinfunction "AU_CL_7") (pintype "bidirectional"))
    )
    (net (code "85") (name "unconnected-(MPU6050-1-AU_DA-Pad6)") (class "Default")
      (node (ref "MPU6050-1") (pin "6") (pinfunction "AU_DA_6") (pintype "bidirectional"))
    )
    (net (code "86") (name "unconnected-(MPU6050-1-NC-Pad2)") (class "Default")
      (node (ref "MPU6050-1") (pin "2") (pinfunction "NC_2") (pintype "bidirectional"))
    )
    (net (code "87") (name "unconnected-(MPU6050-1-NC0-Pad3)") (class "Default")
      (node (ref "MPU6050-1") (pin "3") (pinfunction "NC0_3") (pintype "bidirectional"))
    )
    (net (code "88") (name "unconnected-(MPU6050-1-NC1-Pad4)") (class "Default")
      (node (ref "MPU6050-1") (pin "4") (pinfunction "NC1_4") (pintype "bidirectional"))
    )
    (net (code "89") (name "unconnected-(MPU6050-1-NC2-Pad5)") (class "Default")
      (node (ref "MPU6050-1") (pin "5") (pinfunction "NC2_5") (pintype "bidirectional"))
    )
    (net (code "90") (name "unconnected-(MPU6050-1-NC3-Pad14)") (class "Default")
      (node (ref "MPU6050-1") (pin "14") (pinfunction "NC3_14") (pintype "bidirectional"))
    )
    (net (code "91") (name "unconnected-(MPU6050-1-NC4-Pad15)") (class "Default")
      (node (ref "MPU6050-1") (pin "15") (pinfunction "NC4_15") (pintype "bidirectional"))
    )
    (net (code "92") (name "unconnected-(MPU6050-1-NC5-Pad16)") (class "Default")
      (node (ref "MPU6050-1") (pin "16") (pinfunction "NC5_16") (pintype "bidirectional"))
    )
    (net (code "93") (name "unconnected-(MPU6050-1-NC6-Pad17)") (class "Default")
      (node (ref "MPU6050-1") (pin "17") (pinfunction "NC6_17") (pintype "bidirectional"))
    )
    (net (code "94") (name "unconnected-(MPU6050-1-RESV-Pad19)") (class "Default")
      (node (ref "MPU6050-1") (pin "19") (pinfunction "RESV_19") (pintype "bidirectional"))
    )
    (net (code "95") (name "unconnected-(MPU6050-1-RESV1-Pad21)") (class "Default")
      (node (ref "MPU6050-1") (pin "21") (pinfunction "RESV1_21") (pintype "bidirectional"))
    )
    (net (code "96") (name "unconnected-(MPU6050-1-RESV2-Pad22)") (class "Default")
      (node (ref "MPU6050-1") (pin "22") (pinfunction "RESV2_22") (pintype "bidirectional"))
    )
    (net (code "97") (name "unconnected-(SW1-Pad1)") (class "Default")
      (node (ref "SW1") (pin "1") (pinfunction "1_1") (pintype "bidirectional"))
    )
    (net (code "98") (name "unconnected-(SW1-Pad2)") (class "Default")
      (node (ref "SW1") (pin "2") (pinfunction "2_2") (pintype "bidirectional"))
    )
    (net (code "99") (name "unconnected-(U2-DCC-Pad47)") (class "Default")
      (node (ref "U2") (pin "47") (pinfunction "DCC_47") (pintype "bidirectional"))
    )
    (net (code "100") (name "unconnected-(U2-DEC2-Pad32)") (class "Default")
      (node (ref "U2") (pin "32") (pinfunction "DEC2_32") (pintype "bidirectional"))
    )
    (net (code "101") (name "unconnected-(U2-P0.02-Pad4)") (class "Default")
      (node (ref "U2") (pin "4") (pinfunction "P0.02_4") (pintype "bidirectional"))
    )
    (net (code "102") (name "unconnected-(U2-P0.03-Pad5)") (class "Default")
      (node (ref "U2") (pin "5") (pinfunction "P0.03_5") (pintype "bidirectional"))
    )
    (net (code "103") (name "unconnected-(U2-P0.04-Pad6)") (class "Default")
      (node (ref "U2") (pin "6") (pinfunction "P0.04_6") (pintype "bidirectional"))
    )
    (net (code "104") (name "unconnected-(U2-P0.05-Pad7)") (class "Default")
      (node (ref "U2") (pin "7") (pinfunction "P0.05_7") (pintype "bidirectional"))
    )
    (net (code "105") (name "unconnected-(U2-P0.06-Pad8)") (class "Default")
      (node (ref "U2") (pin "8") (pinfunction "P0.06_8") (pintype "bidirectional"))
    )
    (net (code "106") (name "unconnected-(U2-P0.07-Pad9)") (class "Default")
      (node (ref "U2") (pin "9") (pinfunction "P0.07_9") (pintype "bidirectional"))
    )
    (net (code "107") (name "unconnected-(U2-P0.08-Pad10)") (class "Default")
      (node (ref "U2") (pin "10") (pinfunction "P0.08_10") (pintype "bidirectional"))
    )
    (net (code "108") (name "unconnected-(U2-P0.09-Pad11)") (class "Default")
      (node (ref "U2") (pin "11") (pinfunction "P0.09_11") (pintype "bidirectional"))
    )
    (net (code "109") (name "unconnected-(U2-P0.10-Pad12)") (class "Default")
      (node (ref "U2") (pin "12") (pinfunction "P0.10_12") (pintype "bidirectional"))
    )
    (net (code "110") (name "unconnected-(U2-P0.11-Pad14)") (class "Default")
      (node (ref "U2") (pin "14") (pinfunction "P0.11_14") (pintype "bidirectional"))
    )
    (net (code "111") (name "unconnected-(U2-P0.12-Pad15)") (class "Default")
      (node (ref "U2") (pin "15") (pinfunction "P0.12_15") (pintype "bidirectional"))
    )
    (net (code "112") (name "unconnected-(U2-P0.13-Pad16)") (class "Default")
      (node (ref "U2") (pin "16") (pinfunction "P0.13_16") (pintype "bidirectional"))
    )
    (net (code "113") (name "unconnected-(U2-P0.17-Pad20)") (class "Default")
      (node (ref "U2") (pin "20") (pinfunction "P0.17_20") (pintype "bidirectional"))
    )
    (net (code "114") (name "unconnected-(U2-P0.19-Pad22)") (class "Default")
      (node (ref "U2") (pin "22") (pinfunction "P0.19_22") (pintype "bidirectional"))
    )
    (net (code "115") (name "unconnected-(U2-P0.20-Pad23)") (class "Default")
      (node (ref "U2") (pin "23") (pinfunction "P0.20_23") (pintype "bidirectional"))
    )
    (net (code "116") (name "unconnected-(U2-P0.22-Pad27)") (class "Default")
      (node (ref "U2") (pin "27") (pinfunction "P0.22_27") (pintype "bidirectional"))
    )
    (net (code "117") (name "unconnected-(U2-P0.23-Pad28)") (class "Default")
      (node (ref "U2") (pin "28") (pinfunction "P0.23_28") (pintype "bidirectional"))
    )
    (net (code "118") (name "unconnected-(U2-P0.24-Pad29)") (class "Default")
      (node (ref "U2") (pin "29") (pinfunction "P0.24_29") (pintype "bidirectional"))
    )
    (net (code "119") (name "unconnected-(U2-P0.25-Pad37)") (class "Default")
      (node (ref "U2") (pin "37") (pinfunction "P0.25_37") (pintype "bidirectional"))
    )
    (net (code "120") (name "unconnected-(U2-P0.26-Pad38)") (class "Default")
      (node (ref "U2") (pin "38") (pinfunction "P0.26_38") (pintype "bidirectional"))
    )
    (net (code "121") (name "unconnected-(U2-P0.27-Pad39)") (class "Default")
      (node (ref "U2") (pin "39") (pinfunction "P0.27_39") (pintype "bidirectional"))
    )
    (net (code "122") (name "unconnected-(U2-P0.28-Pad40)") (class "Default")
      (node (ref "U2") (pin "40") (pinfunction "P0.28_40") (pintype "bidirectional"))
    )
    (net (code "123") (name "unconnected-(U2-P0.29-Pad41)") (class "Default")
      (node (ref "U2") (pin "41") (pinfunction "P0.29_41") (pintype "bidirectional"))
    )
    (net (code "124") (name "unconnected-(U2-P0.30-Pad42)") (class "Default")
      (node (ref "U2") (pin "42") (pinfunction "P0.30_42") (pintype "bidirectional"))
    )
    (net (code "125") (name "unconnected-(U2-P0.31-Pad43)") (class "Default")
      (node (ref "U2") (pin "43") (pinfunction "P0.31_43") (pintype "bidirectional"))
    )
    (net (code "126") (name "unconnected-(U2-RESET-Pad24)") (class "Default")
      (node (ref "U2") (pin "24") (pinfunction "RESET_24") (pintype "bidirectional"))
    )
    (net (code "127") (name "unconnected-(U2-SWDCLK-Pad25)") (class "Default")
      (node (ref "U2") (pin "25") (pinfunction "SWDCLK_25") (pintype "bidirectional"))
    )
    (net (code "128") (name "unconnected-(U2-SWDIO-Pad26)") (class "Default")
      (node (ref "U2") (pin "26") (pinfunction "SWDIO_26") (pintype "bidirectional"))
    )
    (net (code "129") (name "unconnected-(U2-VSS2-Pad44)") (class "Default")
      (node (ref "U2") (pin "44") (pinfunction "VSS2_44") (pintype "bidirectional"))
    )
    (net (code "130") (name "unconnected-(U2-XL1-Pad2)") (class "Default")
      (node (ref "U2") (pin "2") (pinfunction "XL1_2") (pintype "bidirectional"))
    )
    (net (code "131") (name "unconnected-(U2-XL2-Pad3)") (class "Default")
      (node (ref "U2") (pin "3") (pinfunction "XL2_3") (pintype "bidirectional"))
    )
    (net (code "132") (name "unconnected-(USB1-ID-Pad4)") (class "Default")
      (node (ref "USB1") (pin "4") (pinfunction "ID_4") (pintype "bidirectional"))
    )
  )
)
